# WiFiCar.net
KiCad netlist of a schematic drawn in Altium Designer
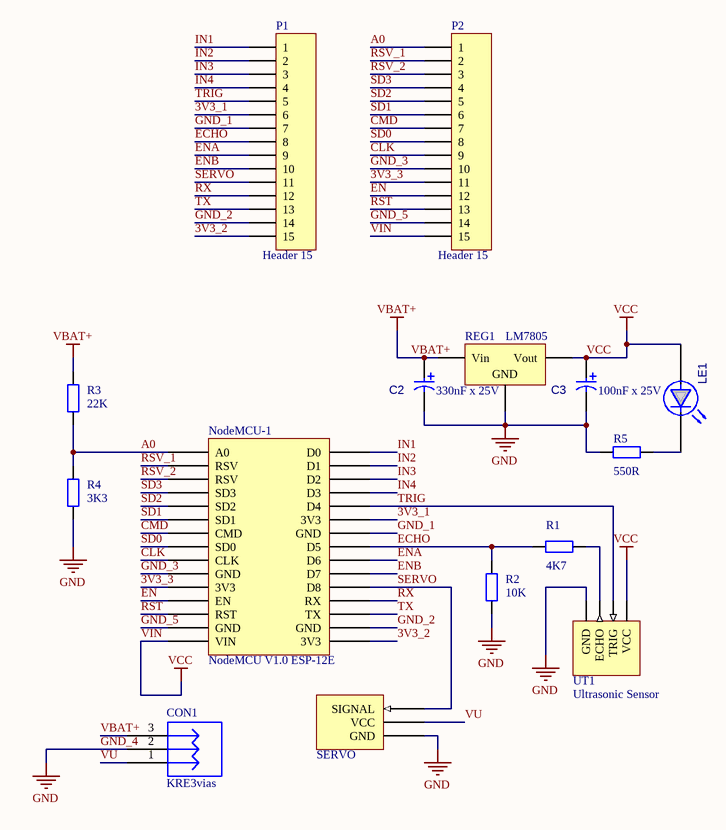
[diagram p0: WiFiCar.SchDoc]

(export (version "E")
  (design (tool "Eeschema 10.0.6"))
  (components
    (comp (ref "C2")
      (value "Capacitor Eletrolitico")
      (footprint "CAPACITOR ELETROLITICO 4x5x1.6mm")
      (fields (field (name "VALOR") "330nF x 25V"))
      (libsource (lib "Altium_Library_Brasil") (part "Capacitor Eletrolitico"))
    )
    (comp (ref "C3")
      (value "Capacitor Eletrolitico")
      (footprint "CAPACITOR ELETROLITICO 4x5x1.6mm")
      (fields (field (name "VALOR") "100nF x 25V"))
      (libsource (lib "Altium_Library_Brasil") (part "Capacitor Eletrolitico"))
    )
    (comp (ref "CON1")
      (value "KRE3vias")
      (footprint "KRE3-3vias")
      (description "Conector 3 vias")
      (libsource (lib "Altium_Library_Brasil") (part "KRE3vias"))
    )
    (comp (ref "LE1")
      (value "LED PTH")
      (footprint "LED PTH 3mm VERDE")
      (libsource (lib "Altium_Library_Brasil") (part "LED PTH"))
    )
    (comp (ref "NodeMCU-1")
      (value "NodeMCU V1.0 ESP-12E")
      (footprint "NodeMCU V1.0 ESP-12E")
      (description "NodeMCU V1.0 ESP8266 (ESP-12E)")
      (libsource (lib "nodemcu") (part "NodeMCU V1.0 ESP-12E"))
    )
    (comp (ref "P1")
      (value "Header 15")
      (footprint "HDR1X15")
      (description "Header, 15-Pin")
      (fields (field (name "PUBLISHER") "Altium Limited"))
      (libsource (lib "Miscellaneous Connectors") (part "Header 15"))
    )
    (comp (ref "P2")
      (value "Header 15")
      (footprint "HDR1X15")
      (description "Header, 15-Pin")
      (fields (field (name "PUBLISHER") "Altium Limited"))
      (libsource (lib "Miscellaneous Connectors") (part "Header 15"))
    )
    (comp (ref "R1")
      (value "4K7")
      (footprint "AXIAL-0.4")
      (description "Resistor")
      (fields (field (name "Comment") "Res2") (field (name "PUBLISHER") "Altium Limited"))
      (libsource (lib "") (part "Res2_2"))
    )
    (comp (ref "R2")
      (value "10K")
      (footprint "AXIAL-0.4")
      (description "Resistor")
      (fields (field (name "Comment") "Res2") (field (name "PUBLISHER") "Altium Limited"))
      (libsource (lib "Miscellaneous Devices") (part "Res2"))
    )
    (comp (ref "R3")
      (value "22K")
      (footprint "AXIAL-0.4")
      (description "Resistor")
      (fields (field (name "Comment") "Res2") (field (name "PUBLISHER") "Altium Limited"))
      (libsource (lib "") (part "Res2_1"))
    )
    (comp (ref "R4")
      (value "3K3")
      (footprint "AXIAL-0.4")
      (description "Resistor")
      (fields (field (name "Comment") "Res2") (field (name "PUBLISHER") "Altium Limited"))
      (libsource (lib "") (part "Res2_1"))
    )
    (comp (ref "R5")
      (value "550R")
      (footprint "AXIAL-0.4")
      (description "Resistor")
      (fields (field (name "Comment") "Res2") (field (name "PUBLISHER") "Altium Limited"))
      (libsource (lib "") (part "Res2_2"))
    )
    (comp (ref "REG1")
      (value "LM7805")
      (footprint "TO-220")
      (description "Regulador de Tensão 5V")
      (fields (field (name "MODELO") "LM7805"))
      (libsource (lib "Altium_Library_Brasil") (part "LM7805"))
    )
    (comp (ref "SERVO") (value "Micro 9g") (libsource (lib "nodemcu_1") (part "MICRO 9G SERVO")))
    (comp (ref "UT1")
      (value "Ultrasonic Sensor")
      (footprint "HC-SR04")
      (libsource (lib "WifiCar") (part "HC-SR04"))
    )
  )
  (nets
    (net (code "1") (name "/3V3_1") (class "Default")
      (node (ref "NodeMCU-1") (pin "3V3") (pinfunction "3V3_3V3") (pintype "passive"))
      (node (ref "P1") (pin "6") (pinfunction "6_6") (pintype "passive"))
    )
    (net (code "2") (name "/3V3_2") (class "Default")
      (node (ref "NodeMCU-1") (pin "3V3") (pinfunction "3V3_3V3") (pintype "passive"))
      (node (ref "P1") (pin "15") (pinfunction "15_15") (pintype "passive"))
    )
    (net (code "3") (name "/3V3_3") (class "Default")
      (node (ref "NodeMCU-1") (pin "3V3") (pinfunction "3V3_3V3") (pintype "passive"))
      (node (ref "P2") (pin "11") (pinfunction "11_11") (pintype "passive"))
    )
    (net (code "4") (name "/A0") (class "Default")
      (node (ref "NodeMCU-1") (pin "A0") (pinfunction "A0_A0") (pintype "passive"))
      (node (ref "P2") (pin "1") (pinfunction "1_1") (pintype "passive"))
      (node (ref "R3") (pin "2") (pinfunction "2_2") (pintype "passive"))
      (node (ref "R4") (pin "1") (pinfunction "1_1") (pintype "passive"))
    )
    (net (code "5") (name "/CLK") (class "Default")
      (node (ref "NodeMCU-1") (pin "CLK") (pinfunction "CLK_CLK") (pintype "passive"))
      (node (ref "P2") (pin "9") (pinfunction "9_9") (pintype "passive"))
    )
    (net (code "6") (name "/CMD") (class "Default")
      (node (ref "NodeMCU-1") (pin "CMD") (pinfunction "CMD_CMD") (pintype "passive"))
      (node (ref "P2") (pin "7") (pinfunction "7_7") (pintype "passive"))
    )
    (net (code "7") (name "/ECHO") (class "Default")
      (node (ref "NodeMCU-1") (pin "D5") (pinfunction "D5_D5") (pintype "passive"))
      (node (ref "P1") (pin "8") (pinfunction "8_8") (pintype "passive"))
      (node (ref "R1") (pin "1") (pinfunction "1_1") (pintype "passive"))
      (node (ref "R2") (pin "2") (pinfunction "2_2") (pintype "passive"))
    )
    (net (code "8") (name "/EN") (class "Default")
      (node (ref "NodeMCU-1") (pin "EN") (pinfunction "EN_EN") (pintype "passive"))
      (node (ref "P2") (pin "12") (pinfunction "12_12") (pintype "passive"))
    )
    (net (code "9") (name "/ENA") (class "Default")
      (node (ref "NodeMCU-1") (pin "D6") (pinfunction "D6_D6") (pintype "passive"))
      (node (ref "P1") (pin "9") (pinfunction "9_9") (pintype "passive"))
    )
    (net (code "10") (name "/ENB") (class "Default")
      (node (ref "NodeMCU-1") (pin "D7") (pinfunction "D7_D7") (pintype "passive"))
      (node (ref "P1") (pin "10") (pinfunction "10_10") (pintype "passive"))
    )
    (net (code "11") (name "/GND_1") (class "Default")
      (node (ref "NodeMCU-1") (pin "GND") (pinfunction "GND_GND") (pintype "passive"))
      (node (ref "P1") (pin "7") (pinfunction "7_7") (pintype "passive"))
    )
    (net (code "12") (name "/GND_2") (class "Default")
      (node (ref "NodeMCU-1") (pin "GND") (pinfunction "GND_GND") (pintype "passive"))
      (node (ref "P1") (pin "14") (pinfunction "14_14") (pintype "passive"))
    )
    (net (code "13") (name "/GND_3") (class "Default")
      (node (ref "NodeMCU-1") (pin "GND") (pinfunction "GND_GND") (pintype "passive"))
      (node (ref "P2") (pin "10") (pinfunction "10_10") (pintype "passive"))
    )
    (net (code "14") (name "/GND_5") (class "Default")
      (node (ref "NodeMCU-1") (pin "GND") (pinfunction "GND_GND") (pintype "passive"))
      (node (ref "P2") (pin "14") (pinfunction "14_14") (pintype "passive"))
    )
    (net (code "15") (name "/IN1") (class "Default")
      (node (ref "NodeMCU-1") (pin "D0") (pinfunction "D0_D0") (pintype "passive"))
      (node (ref "P1") (pin "1") (pinfunction "1_1") (pintype "passive"))
    )
    (net (code "16") (name "/IN2") (class "Default")
      (node (ref "NodeMCU-1") (pin "D1") (pinfunction "D1_D1") (pintype "passive"))
      (node (ref "P1") (pin "2") (pinfunction "2_2") (pintype "passive"))
    )
    (net (code "17") (name "/IN3") (class "Default")
      (node (ref "NodeMCU-1") (pin "D2") (pinfunction "D2_D2") (pintype "passive"))
      (node (ref "P1") (pin "3") (pinfunction "3_3") (pintype "passive"))
    )
    (net (code "18") (name "/IN4") (class "Default")
      (node (ref "NodeMCU-1") (pin "D3") (pinfunction "D3_D3") (pintype "passive"))
      (node (ref "P1") (pin "4") (pinfunction "4_4") (pintype "passive"))
    )
    (net (code "19") (name "/RST") (class "Default")
      (node (ref "NodeMCU-1") (pin "RST") (pinfunction "RST_RST") (pintype "passive"))
      (node (ref "P2") (pin "13") (pinfunction "13_13") (pintype "passive"))
    )
    (net (code "20") (name "/RSV_1") (class "Default")
      (node (ref "NodeMCU-1") (pin "RSV") (pinfunction "RSV_RSV") (pintype "passive"))
      (node (ref "P2") (pin "2") (pinfunction "2_2") (pintype "passive"))
    )
    (net (code "21") (name "/RSV_2") (class "Default")
      (node (ref "NodeMCU-1") (pin "RSV") (pinfunction "RSV_RSV") (pintype "passive"))
      (node (ref "P2") (pin "3") (pinfunction "3_3") (pintype "passive"))
    )
    (net (code "22") (name "/RX") (class "Default")
      (node (ref "NodeMCU-1") (pin "RX") (pinfunction "RX_RX") (pintype "passive"))
      (node (ref "P1") (pin "12") (pinfunction "12_12") (pintype "passive"))
    )
    (net (code "23") (name "/SD0") (class "Default")
      (node (ref "NodeMCU-1") (pin "SD0") (pinfunction "SD0_SD0") (pintype "passive"))
      (node (ref "P2") (pin "8") (pinfunction "8_8") (pintype "passive"))
    )
    (net (code "24") (name "/SD1") (class "Default")
      (node (ref "NodeMCU-1") (pin "SD1") (pinfunction "SD1_SD1") (pintype "passive"))
      (node (ref "P2") (pin "6") (pinfunction "6_6") (pintype "passive"))
    )
    (net (code "25") (name "/SD2") (class "Default")
      (node (ref "NodeMCU-1") (pin "SD2") (pinfunction "SD2_SD2") (pintype "passive"))
      (node (ref "P2") (pin "5") (pinfunction "5_5") (pintype "passive"))
    )
    (net (code "26") (name "/SD3") (class "Default")
      (node (ref "NodeMCU-1") (pin "SD3") (pinfunction "SD3_SD3") (pintype "passive"))
      (node (ref "P2") (pin "4") (pinfunction "4_4") (pintype "passive"))
    )
    (net (code "27") (name "/SERVO") (class "Default")
      (node (ref "NodeMCU-1") (pin "D8") (pinfunction "D8_D8") (pintype "passive"))
      (node (ref "P1") (pin "11") (pinfunction "11_11") (pintype "passive"))
      (node (ref "SERVO") (pin "SIGNAL") (pinfunction "SIGNAL_SIGNAL") (pintype "input"))
    )
    (net (code "28") (name "/TRIG") (class "Default")
      (node (ref "NodeMCU-1") (pin "D4") (pinfunction "D4_D4") (pintype "passive"))
      (node (ref "P1") (pin "5") (pinfunction "5_5") (pintype "passive"))
      (node (ref "UT1") (pin "TRIG") (pinfunction "TRIG_TRIG") (pintype "input"))
    )
    (net (code "29") (name "/TX") (class "Default")
      (node (ref "NodeMCU-1") (pin "TX") (pinfunction "TX_TX") (pintype "passive"))
      (node (ref "P1") (pin "13") (pinfunction "13_13") (pintype "passive"))
    )
    (net (code "30") (name "/VU") (class "Default")
      (node (ref "CON1") (pin "1") (pintype "passive"))
      (node (ref "SERVO") (pin "VCC") (pinfunction "VCC_VCC") (pintype "passive"))
    )
    (net (code "31") (name "GND") (class "Default")
      (node (ref "C2") (pin "2") (pinfunction "MINUS_2") (pintype "passive"))
      (node (ref "C3") (pin "2") (pinfunction "MINUS_2") (pintype "passive"))
      (node (ref "CON1") (pin "2") (pintype "passive"))
      (node (ref "R2") (pin "1") (pinfunction "1_1") (pintype "passive"))
      (node (ref "R4") (pin "2") (pinfunction "2_2") (pintype "passive"))
      (node (ref "R5") (pin "1") (pinfunction "1_1") (pintype "passive"))
      (node (ref "REG1") (pin "2") (pinfunction "GND_2") (pintype "passive"))
      (node (ref "SERVO") (pin "GND") (pinfunction "GND_GND") (pintype "passive"))
      (node (ref "UT1") (pin "GND") (pinfunction "GND_GND") (pintype "power_in"))
    )
    (net (code "32") (name "Net-(LE1-Pad2)") (class "Default")
      (node (ref "LE1") (pin "2") (pintype "passive"))
      (node (ref "R5") (pin "2") (pinfunction "2_2") (pintype "passive"))
    )
    (net (code "33") (name "Net-(R1-Pad2)") (class "Default")
      (node (ref "R1") (pin "2") (pinfunction "2_2") (pintype "passive"))
      (node (ref "UT1") (pin "ECHO") (pinfunction "ECHO_ECHO") (pintype "output"))
    )
    (net (code "34") (name "VBAT+") (class "Default")
      (node (ref "C2") (pin "1") (pinfunction "PLUS_1") (pintype "passive"))
      (node (ref "CON1") (pin "3") (pintype "passive"))
      (node (ref "R3") (pin "1") (pinfunction "1_1") (pintype "passive"))
      (node (ref "REG1") (pin "1") (pinfunction "Vin_1") (pintype "passive"))
    )
    (net (code "35") (name "VCC") (class "Default")
      (node (ref "C3") (pin "1") (pinfunction "PLUS_1") (pintype "passive"))
      (node (ref "LE1") (pin "1") (pintype "passive"))
      (node (ref "NodeMCU-1") (pin "VIN") (pinfunction "VIN_VIN") (pintype "passive"))
      (node (ref "P2") (pin "15") (pinfunction "15_15") (pintype "passive"))
      (node (ref "REG1") (pin "3") (pinfunction "Vout_3") (pintype "passive"))
      (node (ref "UT1") (pin "VCC") (pinfunction "VCC_VCC") (pintype "power_in"))
    )
  )
)
